# Analog_IOs.net
KiCad netlist of a schematic drawn in Altium Designer
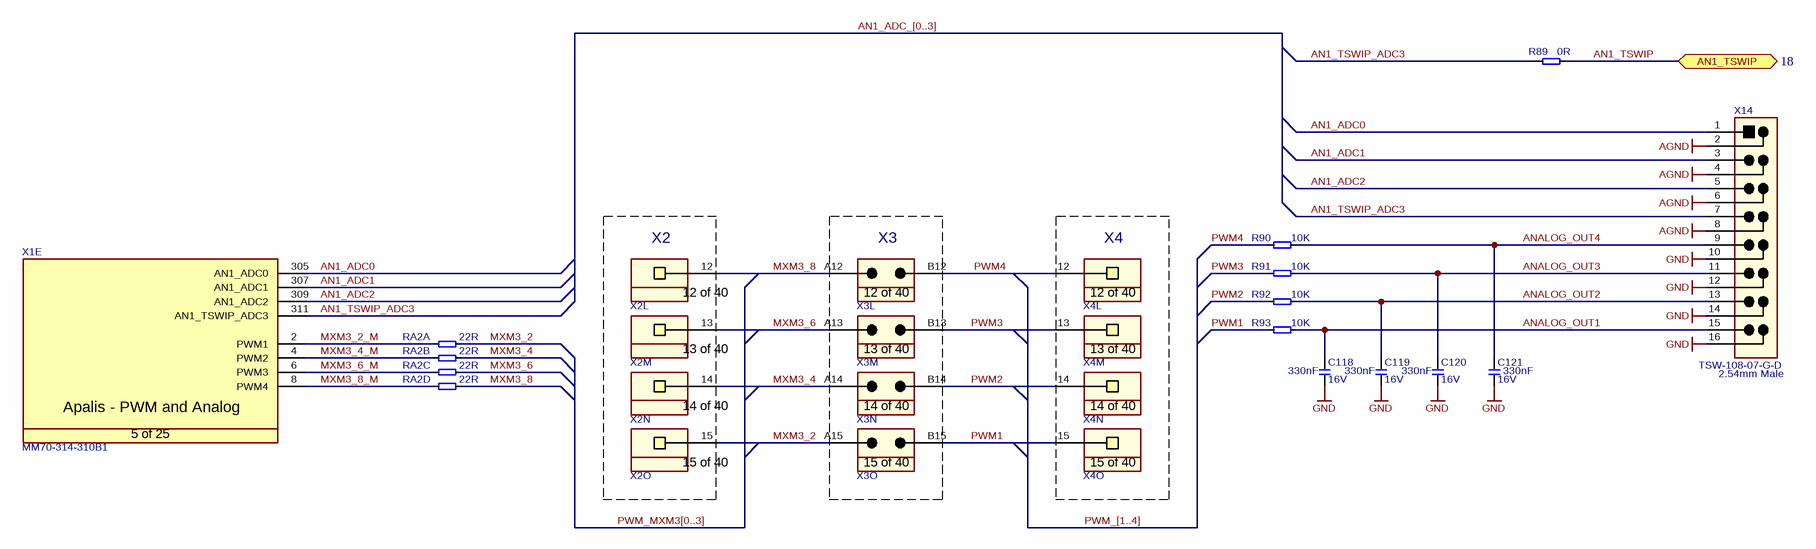
[diagram p0: Analog_IOs.SCHDOC]

(export (version "E")
  (design (tool "Eeschema 10.0.6"))
  (components
    (comp (ref "C118")
      (value "330nF")
      (footprint "T_CAPC0805X125N")
      (description "Capacitor Ceramic X7R 330nF 16V 10% 0805")
      (fields (field (name "TOLERANCE") "10%") (field (name "RATING") "16V"))
      (libsource (lib "Apalis Evaluation Board") (part "C-X7R-330nF-16V-10%-0805"))
    )
    (comp (ref "C119")
      (value "330nF")
      (footprint "T_CAPC0805X125N")
      (description "Capacitor Ceramic X7R 330nF 16V 10% 0805")
      (fields (field (name "TOLERANCE") "10%") (field (name "RATING") "16V"))
      (libsource (lib "Apalis Evaluation Board") (part "C-X7R-330nF-16V-10%-0805"))
    )
    (comp (ref "C120")
      (value "330nF")
      (footprint "T_CAPC0805X125N")
      (description "Capacitor Ceramic X7R 330nF 16V 10% 0805")
      (fields (field (name "TOLERANCE") "10%") (field (name "RATING") "16V"))
      (libsource (lib "Apalis Evaluation Board") (part "C-X7R-330nF-16V-10%-0805"))
    )
    (comp (ref "C121")
      (value "330nF")
      (footprint "T_CAPC0805X125N")
      (description "Capacitor Ceramic X7R 330nF 16V 10% 0805")
      (fields (field (name "TOLERANCE") "10%") (field (name "RATING") "16V"))
      (libsource (lib "Apalis Evaluation Board") (part "C-X7R-330nF-16V-10%-0805"))
    )
    (comp (ref "R89")
      (value "0R")
      (footprint "T_RESC0603X30N")
      (description "Resistor 0 ohm 63mW 1% 0603")
      (fields (field (name "TOLERANCE") "1%"))
      (libsource (lib "Apalis Evaluation Board") (part "R-0R-63mW-1%-0603"))
    )
    (comp (ref "R90")
      (value "10K")
      (footprint "T_RESC0603X30N")
      (description "Resistor 10 Kohm 63mW 5% 0603")
      (fields (field (name "TOLERANCE") "5%"))
      (libsource (lib "Apalis Evaluation Board") (part "R-10KR-63mW-5%-0603"))
    )
    (comp (ref "R91")
      (value "10K")
      (footprint "T_RESC0603X30N")
      (description "Resistor 10 Kohm 63mW 5% 0603")
      (fields (field (name "TOLERANCE") "5%"))
      (libsource (lib "Apalis Evaluation Board") (part "R-10KR-63mW-5%-0603"))
    )
    (comp (ref "R92")
      (value "10K")
      (footprint "T_RESC0603X30N")
      (description "Resistor 10 Kohm 63mW 5% 0603")
      (fields (field (name "TOLERANCE") "5%"))
      (libsource (lib "Apalis Evaluation Board") (part "R-10KR-63mW-5%-0603"))
    )
    (comp (ref "R93")
      (value "10K")
      (footprint "T_RESC0603X30N")
      (description "Resistor 10 Kohm 63mW 5% 0603")
      (fields (field (name "TOLERANCE") "5%"))
      (libsource (lib "Apalis Evaluation Board") (part "R-10KR-63mW-5%-0603"))
    )
    (comp (ref "RA2")
      (value "22R")
      (footprint "T_Resistor_Array_X4")
      (description "Resistor Array 22 R 63mW 5% 1206")
      (fields (field (name "TOLERANCE") "5%"))
      (libsource (lib "Apalis Evaluation Board") (part "RA-22R-63mW-5%-1206-div"))
    )
    (comp (ref "X1")
      (value "CON-JAE-MM70-314-310B1-314-0.5mm")
      (footprint "T_JAE_MM70-314-310B1")
      (description "MXM3 Connector")
      (fields (field (name "MANUFACTURER PART NO.") "MM70-314-310B1"))
      (libsource (lib "Apalis Evaluation Board") (part "CON-JAE-MM70-314-310B1-314-0.5mm"))
    )
    (comp (ref "X2")
      (value "SSW-110-01-G-S")
      (footprint "T_Samtec_SSW-110-01-G-S")
      (description "Receptacle Female Socket 1x40 pin 2.54mm pitch")
      (libsource (lib "Apalis Evaluation Board") (part "CON-Samtec-SSW-110-01-G-S"))
    )
    (comp (ref "X3")
      (value "TSW-110-07-G-D")
      (footprint "T_Samtec_TSW-110-07-G-D")
      (description "Header 2x40 pin 2.54mm pitch")
      (libsource (lib "Apalis Evaluation Board") (part "CON-Samtec-TSW-110-07-G-D"))
    )
    (comp (ref "X4")
      (value "SSW-110-01-G-S")
      (footprint "T_Samtec_SSW-110-01-G-S")
      (description "Receptacle Female Socket 1x40 pin 2.54mm pitch")
      (libsource (lib "") (part "CON-Samtec-SSW-110-01-G-S_1"))
    )
    (comp (ref "X14")
      (value "TSW-108-07-G-D")
      (footprint "T_Samtec_TSW-108-07-G-D")
      (description "Header Male, 2x8 Pins, 2.54mm pitch")
      (fields (field (name "MANUFACTURER PART NO.") "TSW-108-07-G-D"))
      (libsource (lib "Apalis Evaluation Board") (part "CON-Samtec-TSW-108-07-G-D"))
    )
  )
  (nets
    (net (code "13") (name "/AN1_ADC0") (class "Default")
      (node (ref "X1") (pin "305") (pinfunction "AN1_ADC0_305") (pintype "passive"))
      (node (ref "X14") (pin "1") (pinfunction "1_1") (pintype "passive"))
    )
    (net (code "14") (name "/AN1_ADC1") (class "Default")
      (node (ref "X1") (pin "307") (pinfunction "AN1_ADC1_307") (pintype "passive"))
      (node (ref "X14") (pin "3") (pinfunction "3_3") (pintype "passive"))
    )
    (net (code "15") (name "/AN1_ADC2") (class "Default")
      (node (ref "X1") (pin "309") (pinfunction "AN1_ADC2_309") (pintype "passive"))
      (node (ref "X14") (pin "5") (pinfunction "5_5") (pintype "passive"))
    )
    (net (code "17") (name "/AN1_TSWIP") (class "Default")
      (node (ref "R89") (pin "2") (pinfunction "2_2") (pintype "passive"))
    )
    (net (code "18") (name "/AN1_TSWIP_ADC3") (class "Default")
      (node (ref "R89") (pin "1") (pinfunction "1_1") (pintype "passive"))
      (node (ref "X1") (pin "311") (pinfunction "AN1_TSWIP_ADC3_311") (pintype "passive"))
      (node (ref "X14") (pin "7") (pinfunction "7_7") (pintype "passive"))
    )
    (net (code "19") (name "/ANALOG_OUT1") (class "Default")
      (node (ref "C118") (pin "2") (pinfunction "2_2") (pintype "passive"))
      (node (ref "R93") (pin "2") (pinfunction "2_2") (pintype "passive"))
      (node (ref "X14") (pin "15") (pinfunction "15_15") (pintype "passive"))
    )
    (net (code "20") (name "/ANALOG_OUT2") (class "Default")
      (node (ref "C119") (pin "2") (pinfunction "2_2") (pintype "passive"))
      (node (ref "R92") (pin "2") (pinfunction "2_2") (pintype "passive"))
      (node (ref "X14") (pin "13") (pinfunction "13_13") (pintype "passive"))
    )
    (net (code "21") (name "/ANALOG_OUT3") (class "Default")
      (node (ref "C120") (pin "2") (pinfunction "2_2") (pintype "passive"))
      (node (ref "R91") (pin "2") (pinfunction "2_2") (pintype "passive"))
      (node (ref "X14") (pin "11") (pinfunction "11_11") (pintype "passive"))
    )
    (net (code "22") (name "/ANALOG_OUT4") (class "Default")
      (node (ref "C121") (pin "2") (pinfunction "2_2") (pintype "passive"))
      (node (ref "R90") (pin "2") (pinfunction "2_2") (pintype "passive"))
      (node (ref "X14") (pin "9") (pinfunction "9_9") (pintype "passive"))
    )
    (net (code "23") (name "/MXM3_2") (class "Default")
      (node (ref "RA2") (pin "1") (pinfunction "1_1") (pintype "passive"))
      (node (ref "X2") (pin "15") (pinfunction "15_15") (pintype "passive"))
      (node (ref "X3") (pin "A15") (pinfunction "A15_A15") (pintype "passive"))
    )
    (net (code "24") (name "/MXM3_2_M") (class "Default")
      (node (ref "RA2") (pin "5") (pinfunction "5_5") (pintype "passive"))
      (node (ref "X1") (pin "2") (pinfunction "PWM1_2") (pintype "passive"))
    )
    (net (code "25") (name "/MXM3_4") (class "Default")
      (node (ref "RA2") (pin "2") (pinfunction "2_2") (pintype "passive"))
      (node (ref "X2") (pin "14") (pinfunction "14_14") (pintype "passive"))
      (node (ref "X3") (pin "A14") (pinfunction "A14_A14") (pintype "passive"))
    )
    (net (code "26") (name "/MXM3_4_M") (class "Default")
      (node (ref "RA2") (pin "6") (pinfunction "6_6") (pintype "passive"))
      (node (ref "X1") (pin "4") (pinfunction "PWM2_4") (pintype "passive"))
    )
    (net (code "27") (name "/MXM3_6") (class "Default")
      (node (ref "RA2") (pin "3") (pinfunction "3_3") (pintype "passive"))
      (node (ref "X2") (pin "13") (pinfunction "13_13") (pintype "passive"))
      (node (ref "X3") (pin "A13") (pinfunction "A13_A13") (pintype "passive"))
    )
    (net (code "28") (name "/MXM3_6_M") (class "Default")
      (node (ref "RA2") (pin "7") (pinfunction "7_7") (pintype "passive"))
      (node (ref "X1") (pin "6") (pinfunction "PWM3_6") (pintype "passive"))
    )
    (net (code "29") (name "/MXM3_8") (class "Default")
      (node (ref "RA2") (pin "4") (pinfunction "4_4") (pintype "passive"))
      (node (ref "X2") (pin "12") (pinfunction "12_12") (pintype "passive"))
      (node (ref "X3") (pin "A12") (pinfunction "A12_A12") (pintype "passive"))
    )
    (net (code "30") (name "/MXM3_8_M") (class "Default")
      (node (ref "RA2") (pin "8") (pinfunction "8_8") (pintype "passive"))
      (node (ref "X1") (pin "8") (pinfunction "PWM4_8") (pintype "passive"))
    )
    (net (code "31") (name "/PWM1") (class "Default")
      (node (ref "R93") (pin "1") (pinfunction "1_1") (pintype "passive"))
      (node (ref "X3") (pin "B15") (pinfunction "B15_B15") (pintype "passive"))
      (node (ref "X4") (pin "15") (pinfunction "15_15") (pintype "passive"))
    )
    (net (code "32") (name "/PWM2") (class "Default")
      (node (ref "R92") (pin "1") (pinfunction "1_1") (pintype "passive"))
      (node (ref "X3") (pin "B14") (pinfunction "B14_B14") (pintype "passive"))
      (node (ref "X4") (pin "14") (pinfunction "14_14") (pintype "passive"))
    )
    (net (code "33") (name "/PWM3") (class "Default")
      (node (ref "R91") (pin "1") (pinfunction "1_1") (pintype "passive"))
      (node (ref "X3") (pin "B13") (pinfunction "B13_B13") (pintype "passive"))
      (node (ref "X4") (pin "13") (pinfunction "13_13") (pintype "passive"))
    )
    (net (code "34") (name "/PWM4") (class "Default")
      (node (ref "R90") (pin "1") (pinfunction "1_1") (pintype "passive"))
      (node (ref "X3") (pin "B12") (pinfunction "B12_B12") (pintype "passive"))
      (node (ref "X4") (pin "12") (pinfunction "12_12") (pintype "passive"))
    )
    (net (code "37") (name "AGND") (class "Default")
      (node (ref "X14") (pin "2") (pinfunction "2_2") (pintype "passive"))
      (node (ref "X14") (pin "4") (pinfunction "4_4") (pintype "passive"))
      (node (ref "X14") (pin "6") (pinfunction "6_6") (pintype "passive"))
      (node (ref "X14") (pin "8") (pinfunction "8_8") (pintype "passive"))
    )
    (net (code "38") (name "GND") (class "Default")
      (node (ref "C118") (pin "1") (pinfunction "1_1") (pintype "passive"))
      (node (ref "C119") (pin "1") (pinfunction "1_1") (pintype "passive"))
      (node (ref "C120") (pin "1") (pinfunction "1_1") (pintype "passive"))
      (node (ref "C121") (pin "1") (pinfunction "1_1") (pintype "passive"))
      (node (ref "X14") (pin "10") (pinfunction "10_10") (pintype "passive"))
      (node (ref "X14") (pin "12") (pinfunction "12_12") (pintype "passive"))
      (node (ref "X14") (pin "14") (pinfunction "14_14") (pintype "passive"))
      (node (ref "X14") (pin "16") (pinfunction "16_16") (pintype "passive"))
    )
  )
)
